# Volume.net
KiCad netlist of a schematic drawn in EAGLE
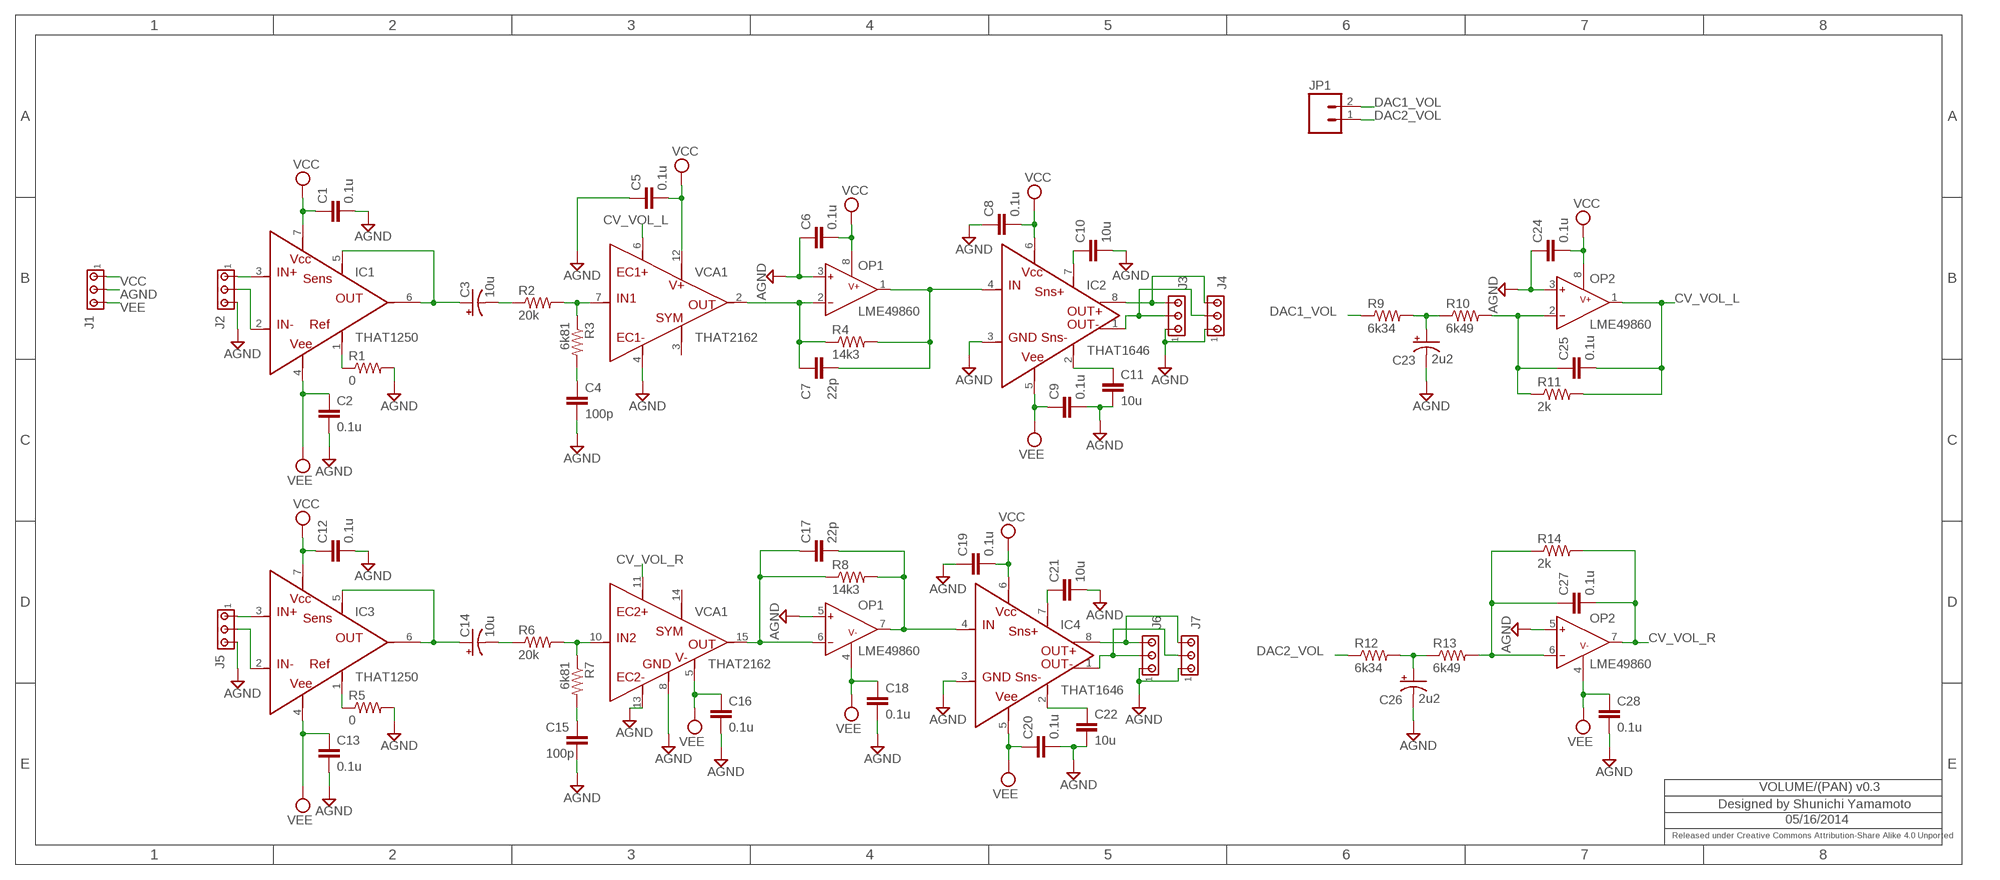
[diagram p0: schematic, sheet 1]

(export (version "E")
  (design (tool "Eeschema 10.0.6"))
  (components
    (comp (ref "C1")
      (value "0.1u")
      (footprint "eagle-import:C2012")
      (libsource (lib "eagle-import") (part "C-EUC2012"))
    )
    (comp (ref "C2")
      (value "0.1u")
      (footprint "eagle-import:C2012")
      (libsource (lib "eagle-import") (part "C-EUC2012"))
    )
    (comp (ref "C3")
      (value "10u")
      (footprint "eagle-import:UD-5X5,8_NICHICON")
      (libsource (lib "eagle-import") (part "CPOL-USUD-5X5,8"))
    )
    (comp (ref "C4")
      (value "100p")
      (footprint "eagle-import:C2012")
      (libsource (lib "eagle-import") (part "C-EUC2012"))
    )
    (comp (ref "C5")
      (value "0.1u")
      (footprint "eagle-import:C2012")
      (libsource (lib "eagle-import") (part "C-EUC2012"))
    )
    (comp (ref "C6")
      (value "0.1u")
      (footprint "eagle-import:C2012")
      (libsource (lib "eagle-import") (part "C-EUC2012"))
    )
    (comp (ref "C7")
      (value "22p")
      (footprint "eagle-import:C2012")
      (libsource (lib "eagle-import") (part "C-EUC2012"))
    )
    (comp (ref "C8")
      (value "0.1u")
      (footprint "eagle-import:C2012")
      (libsource (lib "eagle-import") (part "C-EUC2012"))
    )
    (comp (ref "C9")
      (value "0.1u")
      (footprint "eagle-import:C2012")
      (libsource (lib "eagle-import") (part "C-EUC2012"))
    )
    (comp (ref "C10")
      (value "10u")
      (footprint "eagle-import:C2012")
      (libsource (lib "eagle-import") (part "C-EUC2012"))
    )
    (comp (ref "C11")
      (value "10u")
      (footprint "eagle-import:C2012")
      (libsource (lib "eagle-import") (part "C-EUC2012"))
    )
    (comp (ref "C12")
      (value "0.1u")
      (footprint "eagle-import:C2012")
      (libsource (lib "eagle-import") (part "C-EUC2012"))
    )
    (comp (ref "C13")
      (value "0.1u")
      (footprint "eagle-import:C2012")
      (libsource (lib "eagle-import") (part "C-EUC2012"))
    )
    (comp (ref "C14")
      (value "10u")
      (footprint "eagle-import:UD-5X5,8_NICHICON")
      (libsource (lib "eagle-import") (part "CPOL-USUD-5X5,8"))
    )
    (comp (ref "C15")
      (value "100p")
      (footprint "eagle-import:C2012")
      (libsource (lib "eagle-import") (part "C-EUC2012"))
    )
    (comp (ref "C16")
      (value "0.1u")
      (footprint "eagle-import:C2012")
      (libsource (lib "eagle-import") (part "C-EUC2012"))
    )
    (comp (ref "C17")
      (value "22p")
      (footprint "eagle-import:C2012")
      (libsource (lib "eagle-import") (part "C-EUC2012"))
    )
    (comp (ref "C18")
      (value "0.1u")
      (footprint "eagle-import:C2012")
      (libsource (lib "eagle-import") (part "C-EUC2012"))
    )
    (comp (ref "C19")
      (value "0.1u")
      (footprint "eagle-import:C2012")
      (libsource (lib "eagle-import") (part "C-EUC2012"))
    )
    (comp (ref "C20")
      (value "0.1u")
      (footprint "eagle-import:C2012")
      (libsource (lib "eagle-import") (part "C-EUC2012"))
    )
    (comp (ref "C21")
      (value "10u")
      (footprint "eagle-import:C2012")
      (libsource (lib "eagle-import") (part "C-EUC2012"))
    )
    (comp (ref "C22")
      (value "10u")
      (footprint "eagle-import:C2012")
      (libsource (lib "eagle-import") (part "C-EUC2012"))
    )
    (comp (ref "C23")
      (value "2u2")
      (footprint "eagle-import:UD-5X5,8_NICHICON")
      (libsource (lib "eagle-import") (part "CPOL-USUD-5X5,8"))
    )
    (comp (ref "C24")
      (value "0.1u")
      (footprint "eagle-import:C2012")
      (libsource (lib "eagle-import") (part "C-EUC2012"))
    )
    (comp (ref "C25")
      (value "0.1u")
      (footprint "eagle-import:C2012")
      (libsource (lib "eagle-import") (part "C-EUC2012"))
    )
    (comp (ref "C26")
      (value "2u2")
      (footprint "eagle-import:UD-5X5,8_NICHICON")
      (libsource (lib "eagle-import") (part "CPOL-USUD-5X5,8"))
    )
    (comp (ref "C27")
      (value "0.1u")
      (footprint "eagle-import:C2012")
      (libsource (lib "eagle-import") (part "C-EUC2012"))
    )
    (comp (ref "C28")
      (value "0.1u")
      (footprint "eagle-import:C2012")
      (libsource (lib "eagle-import") (part "C-EUC2012"))
    )
    (comp (ref "IC1")
      (value "THAT1250")
      (footprint "eagle-import:SOIC8")
      (libsource (lib "eagle-import") (part "THAT1250"))
    )
    (comp (ref "IC2")
      (value "THAT1646")
      (footprint "eagle-import:SOIC8")
      (libsource (lib "eagle-import") (part "THAT1646"))
    )
    (comp (ref "IC3")
      (value "THAT1250")
      (footprint "eagle-import:SOIC8")
      (libsource (lib "eagle-import") (part "THAT1250"))
    )
    (comp (ref "IC4")
      (value "THAT1646")
      (footprint "eagle-import:SOIC8")
      (libsource (lib "eagle-import") (part "THAT1646"))
    )
    (comp (ref "J1")
      (value "MTA03-156")
      (footprint "eagle-import:1X3MTA")
      (libsource (lib "eagle-import") (part "MTA03-156"))
    )
    (comp (ref "J2")
      (value "MTA03-100")
      (footprint "eagle-import:10X03MTA")
      (libsource (lib "eagle-import") (part "MTA03-100"))
    )
    (comp (ref "J3")
      (value "MTA03-100")
      (footprint "eagle-import:10X03MTA")
      (libsource (lib "eagle-import") (part "MTA03-100"))
    )
    (comp (ref "J4")
      (value "MTA03-100")
      (footprint "eagle-import:10X03MTA")
      (libsource (lib "eagle-import") (part "MTA03-100"))
    )
    (comp (ref "J5")
      (value "MTA03-100")
      (footprint "eagle-import:10X03MTA")
      (libsource (lib "eagle-import") (part "MTA03-100"))
    )
    (comp (ref "J6")
      (value "MTA03-100")
      (footprint "eagle-import:10X03MTA")
      (libsource (lib "eagle-import") (part "MTA03-100"))
    )
    (comp (ref "J7")
      (value "MTA03-100")
      (footprint "eagle-import:10X03MTA")
      (libsource (lib "eagle-import") (part "MTA03-100"))
    )
    (comp (ref "JP1")
      (value "M02PTH")
      (footprint "eagle-import:1X02")
      (libsource (lib "eagle-import") (part "M02PTH"))
    )
    (comp (ref "OP1")
      (value "LME49860")
      (footprint "eagle-import:SOIC8@1")
      (libsource (lib "eagle-import") (part "LME49860"))
    )
    (comp (ref "OP2")
      (value "LME49860")
      (footprint "eagle-import:SOIC8@1")
      (libsource (lib "eagle-import") (part "LME49860"))
    )
    (comp (ref "R1")
      (value "0")
      (footprint "eagle-import:0805")
      (libsource (lib "eagle-import") (part "RESISTOR0805-RES"))
    )
    (comp (ref "R2")
      (value "20k")
      (footprint "eagle-import:0805")
      (libsource (lib "eagle-import") (part "RESISTOR0805-RES"))
    )
    (comp (ref "R3")
      (value "6k81")
      (footprint "eagle-import:0805")
      (libsource (lib "eagle-import") (part "RESISTOR0805-RES"))
    )
    (comp (ref "R4")
      (value "14k3")
      (footprint "eagle-import:0805")
      (libsource (lib "eagle-import") (part "RESISTOR0805-RES"))
    )
    (comp (ref "R5")
      (value "0")
      (footprint "eagle-import:0805")
      (libsource (lib "eagle-import") (part "RESISTOR0805-RES"))
    )
    (comp (ref "R6")
      (value "20k")
      (footprint "eagle-import:0805")
      (libsource (lib "eagle-import") (part "RESISTOR0805-RES"))
    )
    (comp (ref "R7")
      (value "6k81")
      (footprint "eagle-import:0805")
      (libsource (lib "eagle-import") (part "RESISTOR0805-RES"))
    )
    (comp (ref "R8")
      (value "14k3")
      (footprint "eagle-import:0805")
      (libsource (lib "eagle-import") (part "RESISTOR0805-RES"))
    )
    (comp (ref "R9")
      (value "6k34")
      (footprint "eagle-import:0805")
      (libsource (lib "eagle-import") (part "RESISTOR0805-RES"))
    )
    (comp (ref "R10")
      (value "6k49")
      (footprint "eagle-import:0805")
      (libsource (lib "eagle-import") (part "RESISTOR0805-RES"))
    )
    (comp (ref "R11")
      (value "2k")
      (footprint "eagle-import:0805")
      (libsource (lib "eagle-import") (part "RESISTOR0805-RES"))
    )
    (comp (ref "R12")
      (value "6k34")
      (footprint "eagle-import:0805")
      (libsource (lib "eagle-import") (part "RESISTOR0805-RES"))
    )
    (comp (ref "R13")
      (value "6k49")
      (footprint "eagle-import:0805")
      (libsource (lib "eagle-import") (part "RESISTOR0805-RES"))
    )
    (comp (ref "R14")
      (value "2k")
      (footprint "eagle-import:0805")
      (libsource (lib "eagle-import") (part "RESISTOR0805-RES"))
    )
    (comp (ref "VCA1")
      (value "THAT2162")
      (footprint "eagle-import:QSOP-16")
      (libsource (lib "eagle-import") (part "THAT2162"))
    )
  )
  (nets
    (net (code "1") (name "/CV_VOL_L") (class "Default")
      (node (ref "C25") (pin "2") (pinfunction "2_2") (pintype "passive"))
      (node (ref "OP2") (pin "1") (pinfunction "OUTA_1") (pintype "output"))
      (node (ref "R11") (pin "2") (pinfunction "2_2") (pintype "passive"))
      (node (ref "VCA1") (pin "6") (pinfunction "EC1+_6") (pintype "bidirectional"))
    )
    (net (code "2") (name "/CV_VOL_R") (class "Default")
      (node (ref "C27") (pin "2") (pinfunction "2_2") (pintype "passive"))
      (node (ref "OP2") (pin "7") (pinfunction "OUTB_7") (pintype "output"))
      (node (ref "R14") (pin "2") (pinfunction "2_2") (pintype "passive"))
      (node (ref "VCA1") (pin "11") (pinfunction "EC2+_11") (pintype "input"))
    )
    (net (code "3") (name "/DAC1_VOL") (class "Default")
      (node (ref "JP1") (pin "2") (pinfunction "2_2") (pintype "passive"))
      (node (ref "R9") (pin "1") (pinfunction "1_1") (pintype "passive"))
    )
    (net (code "4") (name "/DAC2_VOL") (class "Default")
      (node (ref "JP1") (pin "1") (pinfunction "1_1") (pintype "passive"))
      (node (ref "R12") (pin "1") (pinfunction "1_1") (pintype "passive"))
    )
    (net (code "5") (name "AGND") (class "Default")
      (node (ref "C1") (pin "2") (pinfunction "2_2") (pintype "passive"))
      (node (ref "C10") (pin "2") (pinfunction "2_2") (pintype "passive"))
      (node (ref "C11") (pin "2") (pinfunction "2_2") (pintype "passive"))
      (node (ref "C12") (pin "2") (pinfunction "2_2") (pintype "passive"))
      (node (ref "C13") (pin "2") (pinfunction "2_2") (pintype "passive"))
      (node (ref "C15") (pin "2") (pinfunction "2_2") (pintype "passive"))
      (node (ref "C16") (pin "2") (pinfunction "2_2") (pintype "passive"))
      (node (ref "C18") (pin "2") (pinfunction "2_2") (pintype "passive"))
      (node (ref "C19") (pin "1") (pinfunction "1_1") (pintype "passive"))
      (node (ref "C2") (pin "2") (pinfunction "2_2") (pintype "passive"))
      (node (ref "C20") (pin "2") (pinfunction "2_2") (pintype "passive"))
      (node (ref "C21") (pin "2") (pinfunction "2_2") (pintype "passive"))
      (node (ref "C22") (pin "2") (pinfunction "2_2") (pintype "passive"))
      (node (ref "C23") (pin "-") (pinfunction "-_-") (pintype "passive"))
      (node (ref "C24") (pin "1") (pinfunction "1_1") (pintype "passive"))
      (node (ref "C26") (pin "-") (pinfunction "-_-") (pintype "passive"))
      (node (ref "C28") (pin "2") (pinfunction "2_2") (pintype "passive"))
      (node (ref "C4") (pin "2") (pinfunction "2_2") (pintype "passive"))
      (node (ref "C5") (pin "1") (pinfunction "1_1") (pintype "passive"))
      (node (ref "C6") (pin "1") (pinfunction "1_1") (pintype "passive"))
      (node (ref "C8") (pin "1") (pinfunction "1_1") (pintype "passive"))
      (node (ref "C9") (pin "2") (pinfunction "2_2") (pintype "passive"))
      (node (ref "IC2") (pin "3") (pinfunction "GND_3") (pintype "input"))
      (node (ref "IC4") (pin "3") (pinfunction "GND_3") (pintype "input"))
      (node (ref "J1") (pin "2") (pinfunction "2_2") (pintype "passive"))
      (node (ref "J2") (pin "3") (pinfunction "3_3") (pintype "passive"))
      (node (ref "J3") (pin "1") (pinfunction "1_1") (pintype "passive"))
      (node (ref "J4") (pin "1") (pinfunction "1_1") (pintype "passive"))
      (node (ref "J5") (pin "3") (pinfunction "3_3") (pintype "passive"))
      (node (ref "J6") (pin "1") (pinfunction "1_1") (pintype "passive"))
      (node (ref "J7") (pin "1") (pinfunction "1_1") (pintype "passive"))
      (node (ref "OP1") (pin "3") (pinfunction "INA+_3") (pintype "input"))
      (node (ref "OP1") (pin "5") (pinfunction "INB+_5") (pintype "input"))
      (node (ref "OP2") (pin "3") (pinfunction "INA+_3") (pintype "input"))
      (node (ref "OP2") (pin "5") (pinfunction "INB+_5") (pintype "input"))
      (node (ref "R1") (pin "2") (pinfunction "2_2") (pintype "passive"))
      (node (ref "R5") (pin "2") (pinfunction "2_2") (pintype "passive"))
      (node (ref "VCA1") (pin "13") (pinfunction "EC2-_13") (pintype "power_in"))
      (node (ref "VCA1") (pin "4") (pinfunction "EC1-_4") (pintype "input"))
      (node (ref "VCA1") (pin "8") (pinfunction "GND_8") (pintype "input"))
    )
    (net (code "6") (name "Net-(C3-Pad-)") (class "Default")
      (node (ref "C3") (pin "-") (pinfunction "-_-") (pintype "passive"))
      (node (ref "R2") (pin "1") (pinfunction "1_1") (pintype "passive"))
    )
    (net (code "7") (name "Net-(C4-Pad1)") (class "Default")
      (node (ref "C4") (pin "1") (pinfunction "1_1") (pintype "passive"))
      (node (ref "R3") (pin "2") (pinfunction "2_2") (pintype "passive"))
    )
    (net (code "8") (name "Net-(C14-Pad-)") (class "Default")
      (node (ref "C14") (pin "-") (pinfunction "-_-") (pintype "passive"))
      (node (ref "R6") (pin "1") (pinfunction "1_1") (pintype "passive"))
    )
    (net (code "9") (name "Net-(C15-Pad1)") (class "Default")
      (node (ref "C15") (pin "1") (pinfunction "1_1") (pintype "passive"))
      (node (ref "R7") (pin "2") (pinfunction "2_2") (pintype "passive"))
    )
    (net (code "10") (name "Net-(C23-Pad+)") (class "Default")
      (node (ref "C23") (pin "+") (pinfunction "+_+") (pintype "passive"))
      (node (ref "R10") (pin "1") (pinfunction "1_1") (pintype "passive"))
      (node (ref "R9") (pin "2") (pinfunction "2_2") (pintype "passive"))
    )
    (net (code "11") (name "Net-(C26-Pad+)") (class "Default")
      (node (ref "C26") (pin "+") (pinfunction "+_+") (pintype "passive"))
      (node (ref "R12") (pin "2") (pinfunction "2_2") (pintype "passive"))
      (node (ref "R13") (pin "1") (pinfunction "1_1") (pintype "passive"))
    )
    (net (code "12") (name "Net-(IC1-IN+)") (class "Default")
      (node (ref "IC1") (pin "3") (pinfunction "IN+_3") (pintype "input"))
      (node (ref "J2") (pin "1") (pinfunction "1_1") (pintype "passive"))
    )
    (net (code "13") (name "Net-(IC1-IN-)") (class "Default")
      (node (ref "IC1") (pin "2") (pinfunction "IN-_2") (pintype "input"))
      (node (ref "J2") (pin "2") (pinfunction "2_2") (pintype "passive"))
    )
    (net (code "14") (name "Net-(IC1-OUT)") (class "Default")
      (node (ref "C3") (pin "+") (pinfunction "+_+") (pintype "passive"))
      (node (ref "IC1") (pin "5") (pinfunction "SENS_5") (pintype "power_in"))
      (node (ref "IC1") (pin "6") (pinfunction "OUT_6") (pintype "output"))
    )
    (net (code "15") (name "Net-(IC1-REF)") (class "Default")
      (node (ref "IC1") (pin "1") (pinfunction "REF_1") (pintype "input"))
      (node (ref "R1") (pin "1") (pinfunction "1_1") (pintype "passive"))
    )
    (net (code "16") (name "Net-(IC2-IN)") (class "Default")
      (node (ref "C7") (pin "2") (pinfunction "2_2") (pintype "passive"))
      (node (ref "IC2") (pin "4") (pinfunction "IN_4") (pintype "input"))
      (node (ref "OP1") (pin "1") (pinfunction "OUTA_1") (pintype "output"))
      (node (ref "R4") (pin "2") (pinfunction "2_2") (pintype "passive"))
    )
    (net (code "17") (name "Net-(IC2-OUT+)") (class "Default")
      (node (ref "IC2") (pin "8") (pinfunction "OUT+_8") (pintype "output"))
      (node (ref "J3") (pin "3") (pinfunction "3_3") (pintype "passive"))
      (node (ref "J4") (pin "3") (pinfunction "3_3") (pintype "passive"))
    )
    (net (code "18") (name "Net-(IC2-OUT-)") (class "Default")
      (node (ref "IC2") (pin "1") (pinfunction "OUT-_1") (pintype "output"))
      (node (ref "J3") (pin "2") (pinfunction "2_2") (pintype "passive"))
      (node (ref "J4") (pin "2") (pinfunction "2_2") (pintype "passive"))
    )
    (net (code "19") (name "Net-(IC2-SNS+)") (class "Default")
      (node (ref "C10") (pin "1") (pinfunction "1_1") (pintype "passive"))
      (node (ref "IC2") (pin "7") (pinfunction "SNS+_7") (pintype "power_in"))
    )
    (net (code "20") (name "Net-(IC2-SNS-)") (class "Default")
      (node (ref "C11") (pin "1") (pinfunction "1_1") (pintype "passive"))
      (node (ref "IC2") (pin "2") (pinfunction "SNS-_2") (pintype "input"))
    )
    (net (code "21") (name "Net-(IC3-IN+)") (class "Default")
      (node (ref "IC3") (pin "3") (pinfunction "IN+_3") (pintype "input"))
      (node (ref "J5") (pin "1") (pinfunction "1_1") (pintype "passive"))
    )
    (net (code "22") (name "Net-(IC3-IN-)") (class "Default")
      (node (ref "IC3") (pin "2") (pinfunction "IN-_2") (pintype "input"))
      (node (ref "J5") (pin "2") (pinfunction "2_2") (pintype "passive"))
    )
    (net (code "23") (name "Net-(IC3-OUT)") (class "Default")
      (node (ref "C14") (pin "+") (pinfunction "+_+") (pintype "passive"))
      (node (ref "IC3") (pin "5") (pinfunction "SENS_5") (pintype "power_in"))
      (node (ref "IC3") (pin "6") (pinfunction "OUT_6") (pintype "output"))
    )
    (net (code "24") (name "Net-(IC3-REF)") (class "Default")
      (node (ref "IC3") (pin "1") (pinfunction "REF_1") (pintype "input"))
      (node (ref "R5") (pin "1") (pinfunction "1_1") (pintype "passive"))
    )
    (net (code "25") (name "Net-(IC4-IN)") (class "Default")
      (node (ref "C17") (pin "2") (pinfunction "2_2") (pintype "passive"))
      (node (ref "IC4") (pin "4") (pinfunction "IN_4") (pintype "input"))
      (node (ref "OP1") (pin "7") (pinfunction "OUTB_7") (pintype "output"))
      (node (ref "R8") (pin "2") (pinfunction "2_2") (pintype "passive"))
    )
    (net (code "26") (name "Net-(IC4-OUT+)") (class "Default")
      (node (ref "IC4") (pin "8") (pinfunction "OUT+_8") (pintype "output"))
      (node (ref "J6") (pin "3") (pinfunction "3_3") (pintype "passive"))
      (node (ref "J7") (pin "3") (pinfunction "3_3") (pintype "passive"))
    )
    (net (code "27") (name "Net-(IC4-OUT-)") (class "Default")
      (node (ref "IC4") (pin "1") (pinfunction "OUT-_1") (pintype "output"))
      (node (ref "J6") (pin "2") (pinfunction "2_2") (pintype "passive"))
      (node (ref "J7") (pin "2") (pinfunction "2_2") (pintype "passive"))
    )
    (net (code "28") (name "Net-(IC4-SNS+)") (class "Default")
      (node (ref "C21") (pin "1") (pinfunction "1_1") (pintype "passive"))
      (node (ref "IC4") (pin "7") (pinfunction "SNS+_7") (pintype "power_in"))
    )
    (net (code "29") (name "Net-(IC4-SNS-)") (class "Default")
      (node (ref "C22") (pin "1") (pinfunction "1_1") (pintype "passive"))
      (node (ref "IC4") (pin "2") (pinfunction "SNS-_2") (pintype "input"))
    )
    (net (code "30") (name "Net-(OP1A-INA-)") (class "Default")
      (node (ref "C7") (pin "1") (pinfunction "1_1") (pintype "passive"))
      (node (ref "OP1") (pin "2") (pinfunction "INA-_2") (pintype "input"))
      (node (ref "R4") (pin "1") (pinfunction "1_1") (pintype "passive"))
      (node (ref "VCA1") (pin "2") (pinfunction "OUT1_2") (pintype "output"))
    )
    (net (code "31") (name "Net-(OP1B-INB-)") (class "Default")
      (node (ref "C17") (pin "1") (pinfunction "1_1") (pintype "passive"))
      (node (ref "OP1") (pin "6") (pinfunction "INB-_6") (pintype "input"))
      (node (ref "R8") (pin "1") (pinfunction "1_1") (pintype "passive"))
      (node (ref "VCA1") (pin "15") (pinfunction "OUT2_15") (pintype "output"))
    )
    (net (code "32") (name "Net-(OP2A-INA-)") (class "Default")
      (node (ref "C25") (pin "1") (pinfunction "1_1") (pintype "passive"))
      (node (ref "OP2") (pin "2") (pinfunction "INA-_2") (pintype "input"))
      (node (ref "R10") (pin "2") (pinfunction "2_2") (pintype "passive"))
      (node (ref "R11") (pin "1") (pinfunction "1_1") (pintype "passive"))
    )
    (net (code "33") (name "Net-(OP2B-INB-)") (class "Default")
      (node (ref "C27") (pin "1") (pinfunction "1_1") (pintype "passive"))
      (node (ref "OP2") (pin "6") (pinfunction "INB-_6") (pintype "input"))
      (node (ref "R13") (pin "2") (pinfunction "2_2") (pintype "passive"))
      (node (ref "R14") (pin "1") (pinfunction "1_1") (pintype "passive"))
    )
    (net (code "34") (name "Net-(VCA1A-IN1)") (class "Default")
      (node (ref "R2") (pin "2") (pinfunction "2_2") (pintype "passive"))
      (node (ref "R3") (pin "1") (pinfunction "1_1") (pintype "passive"))
      (node (ref "VCA1") (pin "7") (pinfunction "IN1_7") (pintype "input"))
    )
    (net (code "35") (name "Net-(VCA1B-IN2)") (class "Default")
      (node (ref "R6") (pin "2") (pinfunction "2_2") (pintype "passive"))
      (node (ref "R7") (pin "1") (pinfunction "1_1") (pintype "passive"))
      (node (ref "VCA1") (pin "10") (pinfunction "IN2_10") (pintype "input"))
    )
    (net (code "36") (name "VCC") (class "Default")
      (node (ref "C1") (pin "1") (pinfunction "1_1") (pintype "passive"))
      (node (ref "C12") (pin "1") (pinfunction "1_1") (pintype "passive"))
      (node (ref "C19") (pin "2") (pinfunction "2_2") (pintype "passive"))
      (node (ref "C24") (pin "2") (pinfunction "2_2") (pintype "passive"))
      (node (ref "C5") (pin "2") (pinfunction "2_2") (pintype "passive"))
      (node (ref "C6") (pin "2") (pinfunction "2_2") (pintype "passive"))
      (node (ref "C8") (pin "2") (pinfunction "2_2") (pintype "passive"))
      (node (ref "IC1") (pin "7") (pinfunction "VCC_7") (pintype "power_in"))
      (node (ref "IC2") (pin "6") (pinfunction "VCC_6") (pintype "bidirectional"))
      (node (ref "IC3") (pin "7") (pinfunction "VCC_7") (pintype "power_in"))
      (node (ref "IC4") (pin "6") (pinfunction "VCC_6") (pintype "bidirectional"))
      (node (ref "J1") (pin "1") (pinfunction "1_1") (pintype "passive"))
      (node (ref "OP1") (pin "8") (pinfunction "V+_8") (pintype "power_in"))
      (node (ref "OP2") (pin "8") (pinfunction "V+_8") (pintype "power_in"))
      (node (ref "VCA1") (pin "12") (pinfunction "V+_12") (pintype "power_in"))
    )
    (net (code "37") (name "VEE") (class "Default")
      (node (ref "C13") (pin "1") (pinfunction "1_1") (pintype "passive"))
      (node (ref "C16") (pin "1") (pinfunction "1_1") (pintype "passive"))
      (node (ref "C18") (pin "1") (pinfunction "1_1") (pintype "passive"))
      (node (ref "C2") (pin "1") (pinfunction "1_1") (pintype "passive"))
      (node (ref "C20") (pin "1") (pinfunction "1_1") (pintype "passive"))
      (node (ref "C28") (pin "1") (pinfunction "1_1") (pintype "passive"))
      (node (ref "C9") (pin "1") (pinfunction "1_1") (pintype "passive"))
      (node (ref "IC1") (pin "4") (pinfunction "VEE_4") (pintype "power_in"))
      (node (ref "IC2") (pin "5") (pinfunction "VEE_5") (pintype "input"))
      (node (ref "IC3") (pin "4") (pinfunction "VEE_4") (pintype "power_in"))
      (node (ref "IC4") (pin "5") (pinfunction "VEE_5") (pintype "input"))
      (node (ref "J1") (pin "3") (pinfunction "3_3") (pintype "passive"))
      (node (ref "OP1") (pin "4") (pinfunction "V-_4") (pintype "power_in"))
      (node (ref "OP2") (pin "4") (pinfunction "V-_4") (pintype "power_in"))
      (node (ref "VCA1") (pin "5") (pinfunction "V-_5") (pintype "input"))
    )
    (net (code "38") (name "unconnected-(VCA1A-SYM1-Pad3)") (class "Default")
      (node (ref "VCA1") (pin "3") (pinfunction "SYM1_3") (pintype "input"))
    )
    (net (code "39") (name "unconnected-(VCA1B-SYM2-Pad14)") (class "Default")
      (node (ref "VCA1") (pin "14") (pinfunction "SYM2_14") (pintype "input"))
    )
  )
)
